# Key_Matrix.net
KiCad netlist of a schematic drawn in Altium Designer
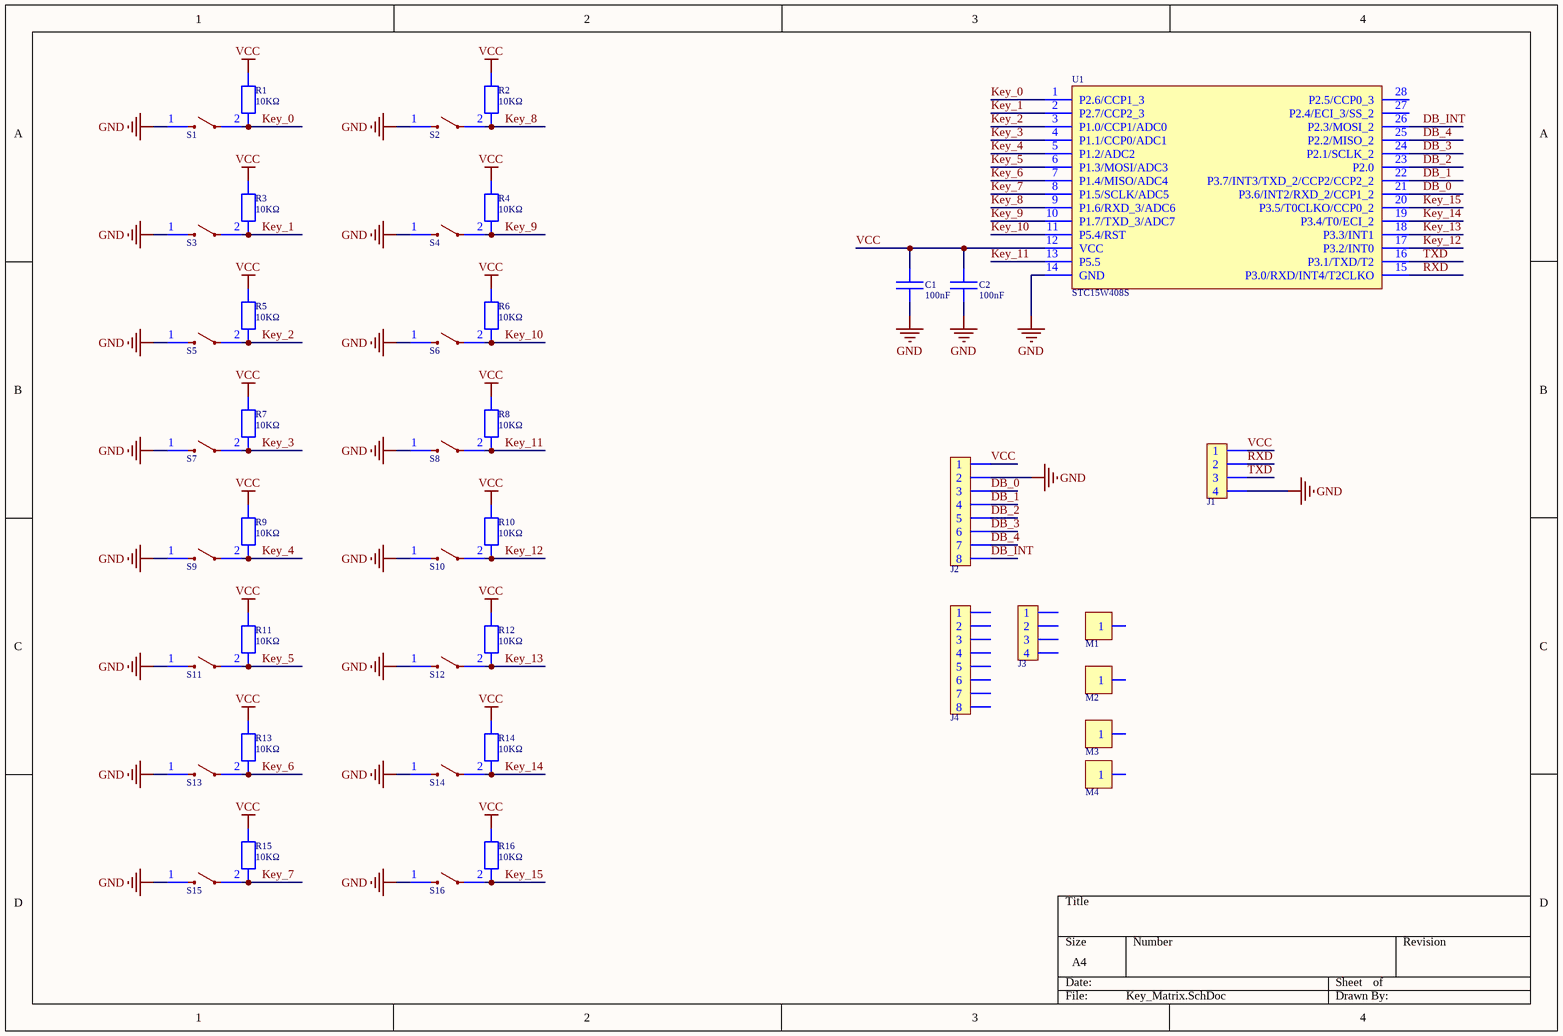
[diagram p0: Key_Matrix.SchDoc]

(export (version "E")
  (design (tool "Eeschema 10.0.6"))
  (components
    (comp (ref "C1")
      (value "100nF")
      (footprint "C0603")
      (libsource (lib "Schematic Library_General") (part "Capacitor_0603"))
    )
    (comp (ref "C2")
      (value "100nF")
      (footprint "C0603")
      (libsource (lib "Schematic Library_General") (part "Capacitor_0603"))
    )
    (comp (ref "J1")
      (value "PinHeader_4Pin")
      (footprint "PinHeader_4Pin-2.54mm")
      (description "Straight Single Row, Square Pitch, 2.54mm")
      (libsource (lib "Schematic Library_General") (part "PinHeader_4Pin"))
    )
    (comp (ref "J2")
      (value "PinHeader_8Pin")
      (footprint "PinHeader_8Pin-2.54mm")
      (description "Straight Single Row, Square Pitch, 2.54mm")
      (libsource (lib "Schematic Library_General") (part "PinHeader_8Pin"))
    )
    (comp (ref "J3")
      (value "PinHeader_4Pin")
      (footprint "PinHeader_4Pin-2.54mm")
      (description "Straight Single Row, Square Pitch, 2.54mm")
      (libsource (lib "Schematic Library_General") (part "PinHeader_4Pin"))
    )
    (comp (ref "J4")
      (value "PinHeader_8Pin")
      (footprint "PinHeader_8Pin-2.54mm")
      (description "Straight Single Row, Square Pitch, 2.54mm")
      (libsource (lib "Schematic Library_General") (part "PinHeader_8Pin"))
    )
    (comp (ref "M1")
      (value "PCB Mounting Hole")
      (footprint "PCB Mounting Hole")
      (description "Mounting Hole")
      (libsource (lib "Schematic Library_General") (part "PCB Mounting Hole"))
    )
    (comp (ref "M2")
      (value "PCB Mounting Hole")
      (footprint "PCB Mounting Hole")
      (description "Mounting Hole")
      (libsource (lib "Schematic Library_General") (part "PCB Mounting Hole"))
    )
    (comp (ref "M3")
      (value "PCB Mounting Hole")
      (footprint "PCB Mounting Hole")
      (description "Mounting Hole")
      (libsource (lib "Schematic Library_General") (part "PCB Mounting Hole"))
    )
    (comp (ref "M4")
      (value "PCB Mounting Hole")
      (footprint "PCB Mounting Hole")
      (description "Mounting Hole")
      (libsource (lib "Schematic Library_General") (part "PCB Mounting Hole"))
    )
    (comp (ref "R1")
      (value "10KΩ")
      (footprint "R0805")
      (libsource (lib "Schematic Library_General") (part "Resistor_0805"))
    )
    (comp (ref "R2")
      (value "10KΩ")
      (footprint "R0805")
      (libsource (lib "Schematic Library_General") (part "Resistor_0805"))
    )
    (comp (ref "R3")
      (value "10KΩ")
      (footprint "R0805")
      (libsource (lib "Schematic Library_General") (part "Resistor_0805"))
    )
    (comp (ref "R4")
      (value "10KΩ")
      (footprint "R0805")
      (libsource (lib "Schematic Library_General") (part "Resistor_0805"))
    )
    (comp (ref "R5")
      (value "10KΩ")
      (footprint "R0805")
      (libsource (lib "Schematic Library_General") (part "Resistor_0805"))
    )
    (comp (ref "R6")
      (value "10KΩ")
      (footprint "R0805")
      (libsource (lib "Schematic Library_General") (part "Resistor_0805"))
    )
    (comp (ref "R7")
      (value "10KΩ")
      (footprint "R0805")
      (libsource (lib "Schematic Library_General") (part "Resistor_0805"))
    )
    (comp (ref "R8")
      (value "10KΩ")
      (footprint "R0805")
      (libsource (lib "Schematic Library_General") (part "Resistor_0805"))
    )
    (comp (ref "R9")
      (value "10KΩ")
      (footprint "R0805")
      (libsource (lib "Schematic Library_General") (part "Resistor_0805"))
    )
    (comp (ref "R10")
      (value "10KΩ")
      (footprint "R0805")
      (libsource (lib "Schematic Library_General") (part "Resistor_0805"))
    )
    (comp (ref "R11")
      (value "10KΩ")
      (footprint "R0805")
      (libsource (lib "Schematic Library_General") (part "Resistor_0805"))
    )
    (comp (ref "R12")
      (value "10KΩ")
      (footprint "R0805")
      (libsource (lib "Schematic Library_General") (part "Resistor_0805"))
    )
    (comp (ref "R13")
      (value "10KΩ")
      (footprint "R0805")
      (libsource (lib "Schematic Library_General") (part "Resistor_0805"))
    )
    (comp (ref "R14")
      (value "10KΩ")
      (footprint "R0805")
      (libsource (lib "Schematic Library_General") (part "Resistor_0805"))
    )
    (comp (ref "R15")
      (value "10KΩ")
      (footprint "R0805")
      (libsource (lib "Schematic Library_General") (part "Resistor_0805"))
    )
    (comp (ref "R16")
      (value "10KΩ")
      (footprint "R0805")
      (libsource (lib "Schematic Library_General") (part "Resistor_0805"))
    )
    (comp (ref "S1")
      (value "CK_RS282G05A3")
      (footprint "Tactile Button_SMD-SPST_L6.1-W3.7-H2.5")
      (libsource (lib "Schematic Library_General") (part "Button_Push_2Pin_SMD"))
    )
    (comp (ref "S2")
      (value "CK_RS282G05A3")
      (footprint "Tactile Button_SMD-SPST_L6.1-W3.7-H2.5")
      (libsource (lib "Schematic Library_General") (part "Button_Push_2Pin_SMD"))
    )
    (comp (ref "S3")
      (value "CK_RS282G05A3")
      (footprint "Tactile Button_SMD-SPST_L6.1-W3.7-H2.5")
      (libsource (lib "Schematic Library_General") (part "Button_Push_2Pin_SMD"))
    )
    (comp (ref "S4")
      (value "CK_RS282G05A3")
      (footprint "Tactile Button_SMD-SPST_L6.1-W3.7-H2.5")
      (libsource (lib "Schematic Library_General") (part "Button_Push_2Pin_SMD"))
    )
    (comp (ref "S5")
      (value "CK_RS282G05A3")
      (footprint "Tactile Button_SMD-SPST_L6.1-W3.7-H2.5")
      (libsource (lib "Schematic Library_General") (part "Button_Push_2Pin_SMD"))
    )
    (comp (ref "S6")
      (value "CK_RS282G05A3")
      (footprint "Tactile Button_SMD-SPST_L6.1-W3.7-H2.5")
      (libsource (lib "Schematic Library_General") (part "Button_Push_2Pin_SMD"))
    )
    (comp (ref "S7")
      (value "CK_RS282G05A3")
      (footprint "Tactile Button_SMD-SPST_L6.1-W3.7-H2.5")
      (libsource (lib "Schematic Library_General") (part "Button_Push_2Pin_SMD"))
    )
    (comp (ref "S8")
      (value "CK_RS282G05A3")
      (footprint "Tactile Button_SMD-SPST_L6.1-W3.7-H2.5")
      (libsource (lib "Schematic Library_General") (part "Button_Push_2Pin_SMD"))
    )
    (comp (ref "S9")
      (value "CK_RS282G05A3")
      (footprint "Tactile Button_SMD-SPST_L6.1-W3.7-H2.5")
      (libsource (lib "Schematic Library_General") (part "Button_Push_2Pin_SMD"))
    )
    (comp (ref "S10")
      (value "CK_RS282G05A3")
      (footprint "Tactile Button_SMD-SPST_L6.1-W3.7-H2.5")
      (libsource (lib "Schematic Library_General") (part "Button_Push_2Pin_SMD"))
    )
    (comp (ref "S11")
      (value "CK_RS282G05A3")
      (footprint "Tactile Button_SMD-SPST_L6.1-W3.7-H2.5")
      (libsource (lib "Schematic Library_General") (part "Button_Push_2Pin_SMD"))
    )
    (comp (ref "S12")
      (value "CK_RS282G05A3")
      (footprint "Tactile Button_SMD-SPST_L6.1-W3.7-H2.5")
      (libsource (lib "Schematic Library_General") (part "Button_Push_2Pin_SMD"))
    )
    (comp (ref "S13")
      (value "CK_RS282G05A3")
      (footprint "Tactile Button_SMD-SPST_L6.1-W3.7-H2.5")
      (libsource (lib "Schematic Library_General") (part "Button_Push_2Pin_SMD"))
    )
    (comp (ref "S14")
      (value "CK_RS282G05A3")
      (footprint "Tactile Button_SMD-SPST_L6.1-W3.7-H2.5")
      (libsource (lib "Schematic Library_General") (part "Button_Push_2Pin_SMD"))
    )
    (comp (ref "S15")
      (value "CK_RS282G05A3")
      (footprint "Tactile Button_SMD-SPST_L6.1-W3.7-H2.5")
      (libsource (lib "Schematic Library_General") (part "Button_Push_2Pin_SMD"))
    )
    (comp (ref "S16")
      (value "CK_RS282G05A3")
      (footprint "Tactile Button_SMD-SPST_L6.1-W3.7-H2.5")
      (libsource (lib "Schematic Library_General") (part "Button_Push_2Pin_SMD"))
    )
    (comp (ref "U1")
      (value "STC15W408S")
      (footprint "SOIC_28Pin-L17.9-W7.5")
      (libsource (lib "Schematic Library_General") (part "STC15W408S_SOP28"))
    )
  )
  (nets
    (net (code "1") (name "/DB_0") (class "Default")
      (node (ref "J2") (pin "3") (pinfunction "3_3") (pintype "passive"))
      (node (ref "U1") (pin "21") (pinfunction "P3.6/INT2/RXD_2/CCP1_2_21") (pintype "passive"))
    )
    (net (code "2") (name "/DB_1") (class "Default")
      (node (ref "J2") (pin "4") (pinfunction "4_4") (pintype "passive"))
      (node (ref "U1") (pin "22") (pinfunction "P3.7/INT3/TXD_2/CCP2/CCP2_2_22") (pintype "passive"))
    )
    (net (code "3") (name "/DB_2") (class "Default")
      (node (ref "J2") (pin "5") (pinfunction "5_5") (pintype "passive"))
      (node (ref "U1") (pin "23") (pinfunction "P2.0_23") (pintype "passive"))
    )
    (net (code "4") (name "/DB_3") (class "Default")
      (node (ref "J2") (pin "6") (pinfunction "6_6") (pintype "passive"))
      (node (ref "U1") (pin "24") (pinfunction "P2.1/SCLK_2_24") (pintype "passive"))
    )
    (net (code "5") (name "/DB_4") (class "Default")
      (node (ref "J2") (pin "7") (pinfunction "7_7") (pintype "passive"))
      (node (ref "U1") (pin "25") (pinfunction "P2.2/MISO_2_25") (pintype "passive"))
    )
    (net (code "6") (name "/DB_INT") (class "Default")
      (node (ref "J2") (pin "8") (pinfunction "8_8") (pintype "passive"))
      (node (ref "U1") (pin "26") (pinfunction "P2.3/MOSI_2_26") (pintype "passive"))
    )
    (net (code "7") (name "/Key_0") (class "Default")
      (node (ref "R1") (pin "1") (pintype "passive"))
      (node (ref "S1") (pin "2") (pintype "passive"))
      (node (ref "U1") (pin "1") (pinfunction "P2.6/CCP1_3_1") (pintype "passive"))
    )
    (net (code "8") (name "/Key_1") (class "Default")
      (node (ref "R3") (pin "1") (pintype "passive"))
      (node (ref "S3") (pin "2") (pintype "passive"))
      (node (ref "U1") (pin "2") (pinfunction "P2.7/CCP2_3_2") (pintype "passive"))
    )
    (net (code "9") (name "/Key_2") (class "Default")
      (node (ref "R5") (pin "1") (pintype "passive"))
      (node (ref "S5") (pin "2") (pintype "passive"))
      (node (ref "U1") (pin "3") (pinfunction "P1.0/CCP1/ADC0_3") (pintype "passive"))
    )
    (net (code "10") (name "/Key_3") (class "Default")
      (node (ref "R7") (pin "1") (pintype "passive"))
      (node (ref "S7") (pin "2") (pintype "passive"))
      (node (ref "U1") (pin "4") (pinfunction "P1.1/CCP0/ADC1_4") (pintype "passive"))
    )
    (net (code "11") (name "/Key_4") (class "Default")
      (node (ref "R9") (pin "1") (pintype "passive"))
      (node (ref "S9") (pin "2") (pintype "passive"))
      (node (ref "U1") (pin "5") (pinfunction "P1.2/ADC2_5") (pintype "passive"))
    )
    (net (code "12") (name "/Key_5") (class "Default")
      (node (ref "R11") (pin "1") (pintype "passive"))
      (node (ref "S11") (pin "2") (pintype "passive"))
      (node (ref "U1") (pin "6") (pinfunction "P1.3/MOSI/ADC3_6") (pintype "passive"))
    )
    (net (code "13") (name "/Key_6") (class "Default")
      (node (ref "R13") (pin "1") (pintype "passive"))
      (node (ref "S13") (pin "2") (pintype "passive"))
      (node (ref "U1") (pin "7") (pinfunction "P1.4/MISO/ADC4_7") (pintype "passive"))
    )
    (net (code "14") (name "/Key_7") (class "Default")
      (node (ref "R15") (pin "1") (pintype "passive"))
      (node (ref "S15") (pin "2") (pintype "passive"))
      (node (ref "U1") (pin "8") (pinfunction "P1.5/SCLK/ADC5_8") (pintype "passive"))
    )
    (net (code "15") (name "/Key_8") (class "Default")
      (node (ref "R2") (pin "1") (pintype "passive"))
      (node (ref "S2") (pin "2") (pintype "passive"))
      (node (ref "U1") (pin "9") (pinfunction "P1.6/RXD_3/ADC6_9") (pintype "passive"))
    )
    (net (code "16") (name "/Key_9") (class "Default")
      (node (ref "R4") (pin "1") (pintype "passive"))
      (node (ref "S4") (pin "2") (pintype "passive"))
      (node (ref "U1") (pin "10") (pinfunction "P1.7/TXD_3/ADC7_10") (pintype "passive"))
    )
    (net (code "17") (name "/Key_10") (class "Default")
      (node (ref "R6") (pin "1") (pintype "passive"))
      (node (ref "S6") (pin "2") (pintype "passive"))
      (node (ref "U1") (pin "11") (pinfunction "P5.4/RST_11") (pintype "passive"))
    )
    (net (code "18") (name "/Key_11") (class "Default")
      (node (ref "R8") (pin "1") (pintype "passive"))
      (node (ref "S8") (pin "2") (pintype "passive"))
      (node (ref "U1") (pin "13") (pinfunction "P5.5_13") (pintype "passive"))
    )
    (net (code "19") (name "/Key_12") (class "Default")
      (node (ref "R10") (pin "1") (pintype "passive"))
      (node (ref "S10") (pin "2") (pintype "passive"))
      (node (ref "U1") (pin "17") (pinfunction "P3.2/INT0_17") (pintype "passive"))
    )
    (net (code "20") (name "/Key_13") (class "Default")
      (node (ref "R12") (pin "1") (pintype "passive"))
      (node (ref "S12") (pin "2") (pintype "passive"))
      (node (ref "U1") (pin "18") (pinfunction "P3.3/INT1_18") (pintype "passive"))
    )
    (net (code "21") (name "/Key_14") (class "Default")
      (node (ref "R14") (pin "1") (pintype "passive"))
      (node (ref "S14") (pin "2") (pintype "passive"))
      (node (ref "U1") (pin "19") (pinfunction "P3.4/T0/ECI_2_19") (pintype "passive"))
    )
    (net (code "22") (name "/Key_15") (class "Default")
      (node (ref "R16") (pin "1") (pintype "passive"))
      (node (ref "S16") (pin "2") (pintype "passive"))
      (node (ref "U1") (pin "20") (pinfunction "P3.5/T0CLKO/CCP0_2_20") (pintype "passive"))
    )
    (net (code "23") (name "/RXD") (class "Default")
      (node (ref "J1") (pin "2") (pinfunction "2_2") (pintype "passive"))
      (node (ref "U1") (pin "15") (pinfunction "P3.0/RXD/INT4/T2CLKO_15") (pintype "passive"))
    )
    (net (code "24") (name "/TXD") (class "Default")
      (node (ref "J1") (pin "3") (pinfunction "3_3") (pintype "passive"))
      (node (ref "U1") (pin "16") (pinfunction "P3.1/TXD/T2_16") (pintype "passive"))
    )
    (net (code "25") (name "GND") (class "Default")
      (node (ref "C1") (pin "1") (pintype "passive"))
      (node (ref "C2") (pin "1") (pintype "passive"))
      (node (ref "J1") (pin "4") (pinfunction "4_4") (pintype "passive"))
      (node (ref "J2") (pin "2") (pinfunction "2_2") (pintype "passive"))
      (node (ref "S1") (pin "1") (pintype "passive"))
      (node (ref "S10") (pin "1") (pintype "passive"))
      (node (ref "S11") (pin "1") (pintype "passive"))
      (node (ref "S12") (pin "1") (pintype "passive"))
      (node (ref "S13") (pin "1") (pintype "passive"))
      (node (ref "S14") (pin "1") (pintype "passive"))
      (node (ref "S15") (pin "1") (pintype "passive"))
      (node (ref "S16") (pin "1") (pintype "passive"))
      (node (ref "S2") (pin "1") (pintype "passive"))
      (node (ref "S3") (pin "1") (pintype "passive"))
      (node (ref "S4") (pin "1") (pintype "passive"))
      (node (ref "S5") (pin "1") (pintype "passive"))
      (node (ref "S6") (pin "1") (pintype "passive"))
      (node (ref "S7") (pin "1") (pintype "passive"))
      (node (ref "S8") (pin "1") (pintype "passive"))
      (node (ref "S9") (pin "1") (pintype "passive"))
      (node (ref "U1") (pin "14") (pinfunction "GND_14") (pintype "passive"))
    )
    (net (code "26") (name "VCC") (class "Default")
      (node (ref "C1") (pin "2") (pintype "passive"))
      (node (ref "C2") (pin "2") (pintype "passive"))
      (node (ref "J1") (pin "1") (pinfunction "1_1") (pintype "passive"))
      (node (ref "J2") (pin "1") (pinfunction "1_1") (pintype "passive"))
      (node (ref "R1") (pin "2") (pintype "passive"))
      (node (ref "R10") (pin "2") (pintype "passive"))
      (node (ref "R11") (pin "2") (pintype "passive"))
      (node (ref "R12") (pin "2") (pintype "passive"))
      (node (ref "R13") (pin "2") (pintype "passive"))
      (node (ref "R14") (pin "2") (pintype "passive"))
      (node (ref "R15") (pin "2") (pintype "passive"))
      (node (ref "R16") (pin "2") (pintype "passive"))
      (node (ref "R2") (pin "2") (pintype "passive"))
      (node (ref "R3") (pin "2") (pintype "passive"))
      (node (ref "R4") (pin "2") (pintype "passive"))
      (node (ref "R5") (pin "2") (pintype "passive"))
      (node (ref "R6") (pin "2") (pintype "passive"))
      (node (ref "R7") (pin "2") (pintype "passive"))
      (node (ref "R8") (pin "2") (pintype "passive"))
      (node (ref "R9") (pin "2") (pintype "passive"))
      (node (ref "U1") (pin "12") (pinfunction "VCC_12") (pintype "passive"))
    )
    (net (code "27") (name "unconnected-(J3-Pad1)") (class "Default")
      (node (ref "J3") (pin "1") (pinfunction "1_1") (pintype "passive"))
    )
    (net (code "28") (name "unconnected-(J3-Pad2)") (class "Default")
      (node (ref "J3") (pin "2") (pinfunction "2_2") (pintype "passive"))
    )
    (net (code "29") (name "unconnected-(J3-Pad3)") (class "Default")
      (node (ref "J3") (pin "3") (pinfunction "3_3") (pintype "passive"))
    )
    (net (code "30") (name "unconnected-(J3-Pad4)") (class "Default")
      (node (ref "J3") (pin "4") (pinfunction "4_4") (pintype "passive"))
    )
    (net (code "31") (name "unconnected-(J4-Pad1)") (class "Default")
      (node (ref "J4") (pin "1") (pinfunction "1_1") (pintype "passive"))
    )
    (net (code "32") (name "unconnected-(J4-Pad2)") (class "Default")
      (node (ref "J4") (pin "2") (pinfunction "2_2") (pintype "passive"))
    )
    (net (code "33") (name "unconnected-(J4-Pad3)") (class "Default")
      (node (ref "J4") (pin "3") (pinfunction "3_3") (pintype "passive"))
    )
    (net (code "34") (name "unconnected-(J4-Pad4)") (class "Default")
      (node (ref "J4") (pin "4") (pinfunction "4_4") (pintype "passive"))
    )
    (net (code "35") (name "unconnected-(J4-Pad5)") (class "Default")
      (node (ref "J4") (pin "5") (pinfunction "5_5") (pintype "passive"))
    )
    (net (code "36") (name "unconnected-(J4-Pad6)") (class "Default")
      (node (ref "J4") (pin "6") (pinfunction "6_6") (pintype "passive"))
    )
    (net (code "37") (name "unconnected-(J4-Pad7)") (class "Default")
      (node (ref "J4") (pin "7") (pinfunction "7_7") (pintype "passive"))
    )
    (net (code "38") (name "unconnected-(J4-Pad8)") (class "Default")
      (node (ref "J4") (pin "8") (pinfunction "8_8") (pintype "passive"))
    )
    (net (code "39") (name "unconnected-(M1-Pad1)") (class "Default")
      (node (ref "M1") (pin "1") (pinfunction "1_1") (pintype "passive"))
    )
    (net (code "40") (name "unconnected-(M2-Pad1)") (class "Default")
      (node (ref "M2") (pin "1") (pinfunction "1_1") (pintype "passive"))
    )
    (net (code "41") (name "unconnected-(M3-Pad1)") (class "Default")
      (node (ref "M3") (pin "1") (pinfunction "1_1") (pintype "passive"))
    )
    (net (code "42") (name "unconnected-(M4-Pad1)") (class "Default")
      (node (ref "M4") (pin "1") (pinfunction "1_1") (pintype "passive"))
    )
    (net (code "43") (name "unconnected-(U1-P2.4{slash}ECI_3{slash}SS_2-Pad27)") (class "Default")
      (node (ref "U1") (pin "27") (pinfunction "P2.4/ECI_3/SS_2_27") (pintype "passive"))
    )
    (net (code "44") (name "unconnected-(U1-P2.5{slash}CCP0_3-Pad28)") (class "Default")
      (node (ref "U1") (pin "28") (pinfunction "P2.5/CCP0_3_28") (pintype "passive"))
    )
  )
)
